# 1-Controller.net
KiCad netlist of a schematic drawn in Altium Designer
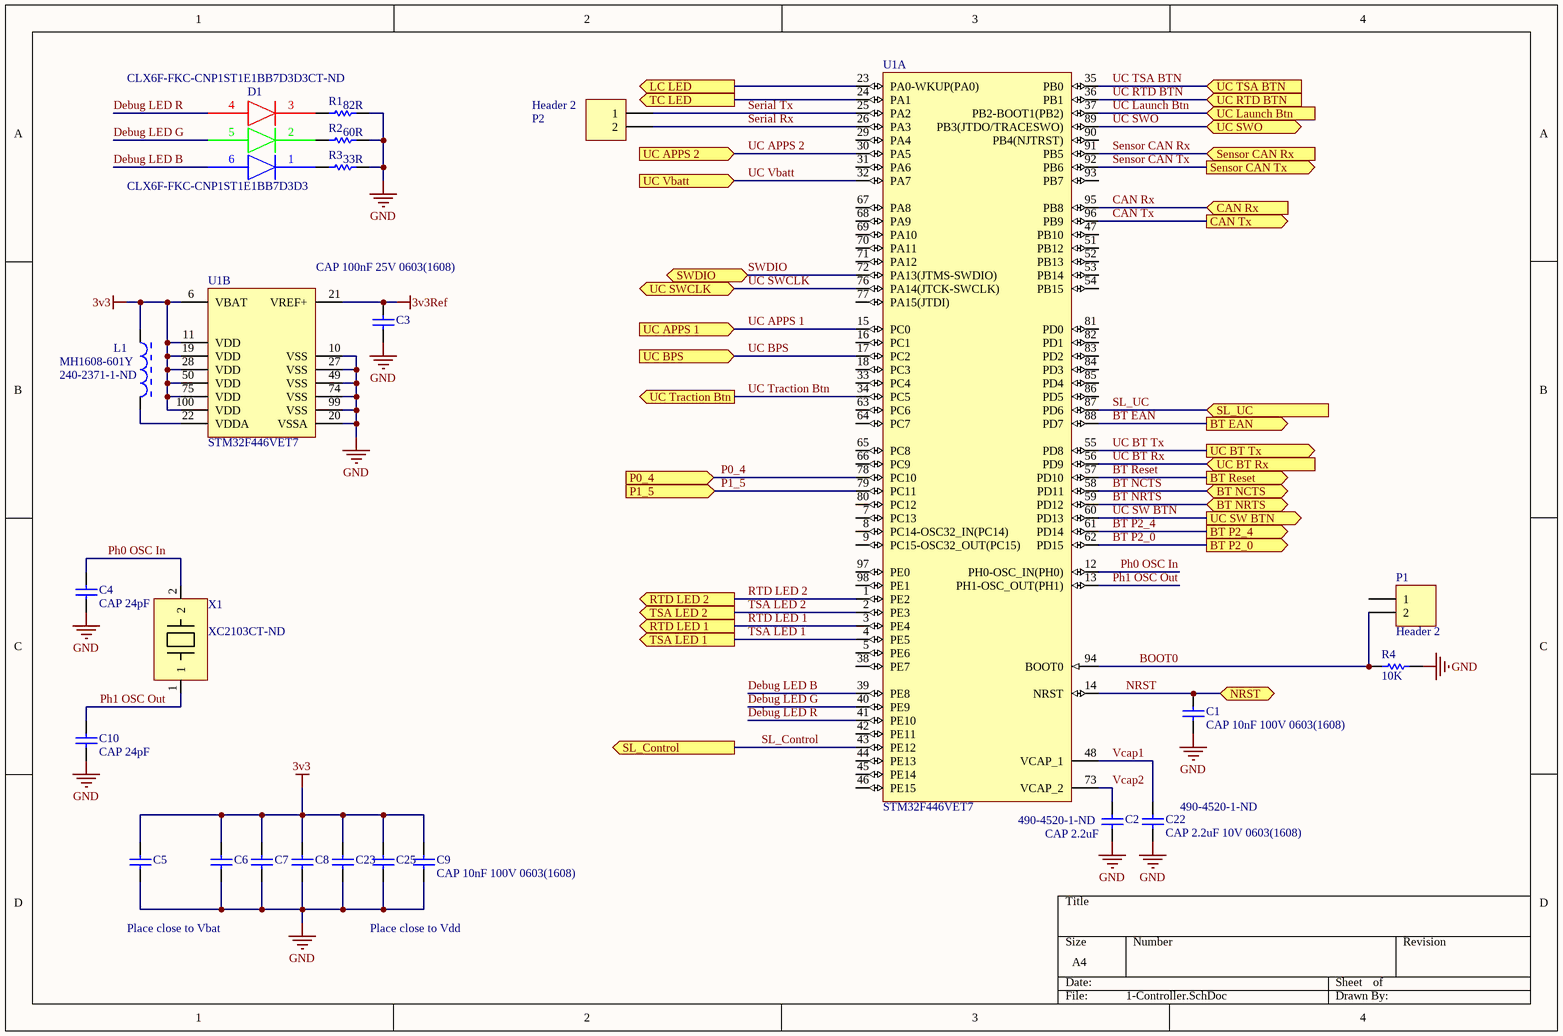
[diagram p0: 1-Controller.SchDoc]

(export (version "E")
  (design (tool "Eeschema 10.0.6"))
  (components
    (comp (ref "C1")
      (value "CAP 10nF 100V 0603(1608)")
      (footprint "CAPC0603(1608)100_M")
      (description "CAP 10nF 100V ±20% 0603 (1608 Metric) Thickness 1mm SMD")
      (fields (field (name "TOLERANCE") "Â±20%"))
      (libsource (lib "Altium Content Vault") (part "CAP"))
    )
    (comp (ref "C2")
      (value "CAP 2.2uF")
      (footprint "CAPC0603(1608)55_N")
      (description "CAP 2.2uF 10V ±10% 0603 (1608 Metric) Thickness 0.55mm SMD")
      (fields (field (name "TOLERANCE") "Â±10%") (field (name "SUPPLIER PART NUMBER 1") "490-4520-1-ND"))
      (libsource (lib "Altium Content Vault") (part "CAP"))
    )
    (comp (ref "C3")
      (value "CAP 100nF 25V 0603(1608)")
      (footprint "CAPC0603(1608)100_N")
      (description "CAP 100nF 25V ±20% 0603 (1608 Metric) Thickness 1mm SMD")
      (fields (field (name "TOLERANCE") "Â±20%"))
      (libsource (lib "Altium Content Vault") (part "CAP"))
    )
    (comp (ref "C4")
      (value "CAP 24pF")
      (footprint "CAPC0603(1608)100_N")
      (description "CAP 24pF 16V ±2% 0603 (1608 Metric) Thickness 1mm SMD")
      (fields (field (name "TOLERANCE") "Â±2%"))
      (libsource (lib "Altium Content Vault") (part "CAP"))
    )
    (comp (ref "C5")
      (value "CAP 10nF 100V 0603(1608)")
      (footprint "CAPC0603(1608)100_M")
      (description "CAP 10nF 100V ±20% 0603 (1608 Metric) Thickness 1mm SMD")
      (fields (field (name "TOLERANCE") "Â±20%"))
      (libsource (lib "Altium Content Vault") (part "CAP"))
    )
    (comp (ref "C6")
      (value "CAP 10nF 100V 0603(1608)")
      (footprint "CAPC0603(1608)100_M")
      (description "CAP 10nF 100V ±20% 0603 (1608 Metric) Thickness 1mm SMD")
      (fields (field (name "TOLERANCE") "Â±20%"))
      (libsource (lib "Altium Content Vault") (part "CAP"))
    )
    (comp (ref "C7")
      (value "CAP 10nF 100V 0603(1608)")
      (footprint "CAPC0603(1608)100_M")
      (description "CAP 10nF 100V ±20% 0603 (1608 Metric) Thickness 1mm SMD")
      (fields (field (name "TOLERANCE") "Â±20%"))
      (libsource (lib "Altium Content Vault") (part "CAP"))
    )
    (comp (ref "C8")
      (value "CAP 10nF 100V 0603(1608)")
      (footprint "CAPC0603(1608)100_M")
      (description "CAP 10nF 100V ±20% 0603 (1608 Metric) Thickness 1mm SMD")
      (fields (field (name "TOLERANCE") "Â±20%"))
      (libsource (lib "Altium Content Vault") (part "CAP"))
    )
    (comp (ref "C9")
      (value "CAP 10nF 100V 0603(1608)")
      (footprint "CAPC0603(1608)100_M")
      (description "CAP 10nF 100V ±20% 0603 (1608 Metric) Thickness 1mm SMD")
      (fields (field (name "TOLERANCE") "Â±20%"))
      (libsource (lib "Altium Content Vault") (part "CAP"))
    )
    (comp (ref "C10")
      (value "CAP 24pF")
      (footprint "CAPC0603(1608)100_N")
      (description "CAP 24pF 16V ±2% 0603 (1608 Metric) Thickness 1mm SMD")
      (fields (field (name "TOLERANCE") "Â±2%"))
      (libsource (lib "Altium Content Vault") (part "CAP"))
    )
    (comp (ref "C22")
      (value "CAP 2.2uF 10V 0603(1608)")
      (footprint "CAPC0603(1608)55_N")
      (description "CAP 2.2uF 10V ±10% 0603 (1608 Metric) Thickness 0.55mm SMD")
      (fields (field (name "TOLERANCE") "Â±10%") (field (name "SUPPLIER PART NUMBER 1") "490-4520-1-ND"))
      (libsource (lib "Altium Content Vault") (part "CAP"))
    )
    (comp (ref "C23")
      (value "CAP 10nF 100V 0603(1608)")
      (footprint "CAPC0603(1608)100_M")
      (description "CAP 10nF 100V ±20% 0603 (1608 Metric) Thickness 1mm SMD")
      (fields (field (name "TOLERANCE") "Â±20%"))
      (libsource (lib "Altium Content Vault") (part "CAP"))
    )
    (comp (ref "C25")
      (value "CAP 10nF 100V 0603(1608)")
      (footprint "CAPC0603(1608)100_M")
      (description "CAP 10nF 100V ±20% 0603 (1608 Metric) Thickness 1mm SMD")
      (fields (field (name "TOLERANCE") "Â±20%"))
      (libsource (lib "Altium Content Vault") (part "CAP"))
    )
    (comp (ref "D1")
      (value "CLX6F-FKC-CNP1ST1E1BB7D3D3")
      (footprint "CLX6C-FKB")
      (fields (field (name "SUPPLIER PART NUMBER 1") "CLX6F-FKC-CNP1ST1E1BB7D3D3CT-ND"))
      (libsource (lib "VCB_2019") (part "LED - CLX6F-FKC-CNP1ST1E1BB7D3D3"))
    )
    (comp (ref "L1")
      (value "MH1608-601Y")
      (footprint "BOUR-MH1608_V")
      (description "Chip Bead, 600 Ohm, 1 A, -55 to 125 degC, 2-Pin SMD (0603), RoHS, Tape and Reel")
      (fields (field (name "MANUFACTURER") "Bourns") (field (name "SUPPLIER PART NUMBER 1") "240-2371-1-ND"))
      (libsource (lib "Altium Content Vault") (part "IND-FB-2"))
    )
    (comp (ref "P1")
      (value "Header 2")
      (footprint "HDR1X2")
      (description "Header, 2-Pin")
      (fields (field (name "PUBLISHER") "Altium Limited"))
      (libsource (lib "Miscellaneous Connectors") (part "Header 2"))
    )
    (comp (ref "P2")
      (value "Header 2")
      (footprint "HDR1X2")
      (description "Header, 2-Pin")
      (fields (field (name "PUBLISHER") "Altium Limited"))
      (libsource (lib "") (part "Header 2_1"))
    )
    (comp (ref "R1")
      (value "82R")
      (footprint "RESC0603(1608)_N")
      (description "82R 0.1W 5% 0603 (1608 Metric)  SMD")
      (fields (field (name "TOLERANCE") "5 %") (field (name "POWER") "0.1 W"))
      (libsource (lib "Altium Content Vault") (part "RES"))
    )
    (comp (ref "R2")
      (value "60R")
      (footprint "RESC0603(1608)_N")
      (description "60R4 0.1W 1% 0603 (1608 Metric)  SMD")
      (fields (field (name "TOLERANCE") "1 %") (field (name "POWER") "0.1 W"))
      (libsource (lib "Altium Content Vault") (part "RES"))
    )
    (comp (ref "R3")
      (value "33R")
      (footprint "RESC0603(1608)_N")
      (description "33R 0.1W 5% 0603 (1608 Metric)  SMD")
      (fields (field (name "TOLERANCE") "5 %") (field (name "POWER") "0.1 W"))
      (libsource (lib "Altium Content Vault") (part "RES"))
    )
    (comp (ref "R4")
      (value "10K")
      (footprint "RESC0603(1608)_N")
      (description "10K 0.1W 5% 0603 (1608 Metric)  SMD")
      (fields (field (name "TOLERANCE") "5 %") (field (name "POWER") "0.1 W"))
      (libsource (lib "Altium Content Vault") (part "RES"))
    )
    (comp (ref "U1")
      (value "STM32F446VET7")
      (footprint "STM-LQFP100_L")
      (libsource (lib "Altium Content Vault") (part "MC-ARM-STM32F446-LQFP100"))
    )
    (comp (ref "X1")
      (value "7A-8.000MAAJ-T")
      (footprint "2-SMD, No Lead")
      (fields
        (field (name "MANUFACTURER") "TXC CORPORATION")
        (field (name "SUPPLIER PART NUMBER 1") "XC2103CT-ND")
      )
      (libsource (lib "VCU Library") (part "8MHz crystal, 7A-8.000MAAJ-T"))
    )
  )
  (nets
    (net (code "1") (name "/BOOT0") (class "Default")
      (node (ref "P1") (pin "2") (pinfunction "2_2") (pintype "passive"))
      (node (ref "R4") (pin "1") (pinfunction "1_1") (pintype "passive"))
      (node (ref "U1") (pin "94") (pinfunction "BOOT0_94") (pintype "input"))
    )
    (net (code "2") (name "/BT EAN") (class "Default")
      (node (ref "U1") (pin "88") (pinfunction "PD7_88") (pintype "bidirectional"))
    )
    (net (code "3") (name "/BT NCTS") (class "Default")
      (node (ref "U1") (pin "58") (pinfunction "PD11_58") (pintype "bidirectional"))
    )
    (net (code "4") (name "/BT NRTS") (class "Default")
      (node (ref "U1") (pin "59") (pinfunction "PD12_59") (pintype "bidirectional"))
    )
    (net (code "5") (name "/BT P2_0") (class "Default")
      (node (ref "U1") (pin "62") (pinfunction "PD15_62") (pintype "bidirectional"))
    )
    (net (code "6") (name "/BT P2_4") (class "Default")
      (node (ref "U1") (pin "61") (pinfunction "PD14_61") (pintype "bidirectional"))
    )
    (net (code "7") (name "/BT Reset") (class "Default")
      (node (ref "U1") (pin "57") (pinfunction "PD10_57") (pintype "bidirectional"))
    )
    (net (code "8") (name "/CAN Rx") (class "Default")
      (node (ref "U1") (pin "95") (pinfunction "PB8_95") (pintype "bidirectional"))
    )
    (net (code "9") (name "/CAN Tx") (class "Default")
      (node (ref "U1") (pin "96") (pinfunction "PB9_96") (pintype "bidirectional"))
    )
    (net (code "10") (name "/Debug LED B") (class "Default")
      (node (ref "D1") (pin "6") (pinfunction "B_6") (pintype "passive"))
      (node (ref "U1") (pin "39") (pinfunction "PE8_39") (pintype "bidirectional"))
    )
    (net (code "11") (name "/Debug LED G") (class "Default")
      (node (ref "D1") (pin "5") (pinfunction "G_5") (pintype "passive"))
      (node (ref "U1") (pin "40") (pinfunction "PE9_40") (pintype "bidirectional"))
    )
    (net (code "12") (name "/Debug LED R") (class "Default")
      (node (ref "D1") (pin "4") (pinfunction "R_4") (pintype "passive"))
      (node (ref "U1") (pin "41") (pinfunction "PE10_41") (pintype "bidirectional"))
    )
    (net (code "13") (name "/LC LED") (class "Default")
      (node (ref "U1") (pin "23") (pinfunction "PA0-WKUP(PA0)_23") (pintype "bidirectional"))
    )
    (net (code "14") (name "/NRST") (class "Default")
      (node (ref "C1") (pin "2") (pinfunction "2_2") (pintype "passive"))
      (node (ref "U1") (pin "14") (pinfunction "NRST_14") (pintype "bidirectional"))
    )
    (net (code "15") (name "/P0_4") (class "Default")
      (node (ref "U1") (pin "78") (pinfunction "PC10_78") (pintype "bidirectional"))
    )
    (net (code "16") (name "/P1_5") (class "Default")
      (node (ref "U1") (pin "79") (pinfunction "PC11_79") (pintype "bidirectional"))
    )
    (net (code "17") (name "/Ph0 OSC In") (class "Default")
      (node (ref "C4") (pin "2") (pinfunction "2_2") (pintype "passive"))
      (node (ref "U1") (pin "12") (pinfunction "PH0-OSC_IN(PH0)_12") (pintype "bidirectional"))
      (node (ref "X1") (pin "2") (pinfunction "2_2") (pintype "passive"))
    )
    (net (code "18") (name "/Ph1 OSC Out") (class "Default")
      (node (ref "C10") (pin "2") (pinfunction "2_2") (pintype "passive"))
      (node (ref "U1") (pin "13") (pinfunction "PH1-OSC_OUT(PH1)_13") (pintype "bidirectional"))
      (node (ref "X1") (pin "1") (pinfunction "1_1") (pintype "passive"))
    )
    (net (code "19") (name "/RTD LED 1") (class "Default")
      (node (ref "U1") (pin "3") (pinfunction "PE4_3") (pintype "bidirectional"))
    )
    (net (code "20") (name "/RTD LED 2") (class "Default")
      (node (ref "U1") (pin "1") (pinfunction "PE2_1") (pintype "bidirectional"))
    )
    (net (code "21") (name "/SL_Control") (class "Default")
      (node (ref "U1") (pin "43") (pinfunction "PE12_43") (pintype "bidirectional"))
    )
    (net (code "22") (name "/SL_UC") (class "Default")
      (node (ref "U1") (pin "87") (pinfunction "PD6_87") (pintype "bidirectional"))
    )
    (net (code "23") (name "/SWDIO") (class "Default")
      (node (ref "U1") (pin "72") (pinfunction "PA13(JTMS-SWDIO)_72") (pintype "bidirectional"))
    )
    (net (code "24") (name "/Sensor CAN Rx") (class "Default")
      (node (ref "U1") (pin "91") (pinfunction "PB5_91") (pintype "bidirectional"))
    )
    (net (code "25") (name "/Sensor CAN Tx") (class "Default")
      (node (ref "U1") (pin "92") (pinfunction "PB6_92") (pintype "bidirectional"))
    )
    (net (code "26") (name "/Serial Rx") (class "Default")
      (node (ref "P2") (pin "2") (pinfunction "2_2") (pintype "passive"))
      (node (ref "U1") (pin "26") (pinfunction "PA3_26") (pintype "bidirectional"))
    )
    (net (code "27") (name "/Serial Tx") (class "Default")
      (node (ref "P2") (pin "1") (pinfunction "1_1") (pintype "passive"))
      (node (ref "U1") (pin "25") (pinfunction "PA2_25") (pintype "bidirectional"))
    )
    (net (code "28") (name "/TC LED") (class "Default")
      (node (ref "U1") (pin "24") (pinfunction "PA1_24") (pintype "bidirectional"))
    )
    (net (code "29") (name "/TSA LED 1") (class "Default")
      (node (ref "U1") (pin "4") (pinfunction "PE5_4") (pintype "bidirectional"))
    )
    (net (code "30") (name "/TSA LED 2") (class "Default")
      (node (ref "U1") (pin "2") (pinfunction "PE3_2") (pintype "bidirectional"))
    )
    (net (code "31") (name "/UC APPS 1") (class "Default")
      (node (ref "U1") (pin "15") (pinfunction "PC0_15") (pintype "bidirectional"))
    )
    (net (code "32") (name "/UC APPS 2") (class "Default")
      (node (ref "U1") (pin "30") (pinfunction "PA5_30") (pintype "bidirectional"))
    )
    (net (code "33") (name "/UC BPS") (class "Default")
      (node (ref "U1") (pin "17") (pinfunction "PC2_17") (pintype "bidirectional"))
    )
    (net (code "34") (name "/UC BT Rx") (class "Default")
      (node (ref "U1") (pin "56") (pinfunction "PD9_56") (pintype "bidirectional"))
    )
    (net (code "35") (name "/UC BT Tx") (class "Default")
      (node (ref "U1") (pin "55") (pinfunction "PD8_55") (pintype "bidirectional"))
    )
    (net (code "36") (name "/UC Launch Btn") (class "Default")
      (node (ref "U1") (pin "37") (pinfunction "PB2-BOOT1(PB2)_37") (pintype "bidirectional"))
    )
    (net (code "37") (name "/UC RTD BTN") (class "Default")
      (node (ref "U1") (pin "36") (pinfunction "PB1_36") (pintype "bidirectional"))
    )
    (net (code "38") (name "/UC SW BTN") (class "Default")
      (node (ref "U1") (pin "60") (pinfunction "PD13_60") (pintype "bidirectional"))
    )
    (net (code "39") (name "/UC SWCLK") (class "Default")
      (node (ref "U1") (pin "76") (pinfunction "PA14(JTCK-SWCLK)_76") (pintype "bidirectional"))
    )
    (net (code "40") (name "/UC SWO") (class "Default")
      (node (ref "U1") (pin "89") (pinfunction "PB3(JTDO/TRACESWO)_89") (pintype "bidirectional"))
    )
    (net (code "41") (name "/UC TSA BTN") (class "Default")
      (node (ref "U1") (pin "35") (pinfunction "PB0_35") (pintype "bidirectional"))
    )
    (net (code "42") (name "/UC Traction Btn") (class "Default")
      (node (ref "U1") (pin "34") (pinfunction "PC5_34") (pintype "bidirectional"))
    )
    (net (code "43") (name "/UC Vbatt") (class "Default")
      (node (ref "U1") (pin "32") (pinfunction "PA7_32") (pintype "bidirectional"))
    )
    (net (code "44") (name "/Vcap1") (class "Default")
      (node (ref "C22") (pin "2") (pinfunction "2_2") (pintype "passive"))
      (node (ref "U1") (pin "48") (pinfunction "VCAP_1_48") (pintype "passive"))
    )
    (net (code "45") (name "/Vcap2") (class "Default")
      (node (ref "C2") (pin "2") (pinfunction "2_2") (pintype "passive"))
      (node (ref "U1") (pin "73") (pinfunction "VCAP_2_73") (pintype "passive"))
    )
    (net (code "46") (name "3v3") (class "Default")
      (node (ref "C23") (pin "2") (pinfunction "2_2") (pintype "passive"))
      (node (ref "C25") (pin "2") (pinfunction "2_2") (pintype "passive"))
      (node (ref "C5") (pin "2") (pinfunction "2_2") (pintype "passive"))
      (node (ref "C6") (pin "2") (pinfunction "2_2") (pintype "passive"))
      (node (ref "C7") (pin "2") (pinfunction "2_2") (pintype "passive"))
      (node (ref "C8") (pin "2") (pinfunction "2_2") (pintype "passive"))
      (node (ref "C9") (pin "2") (pinfunction "2_2") (pintype "passive"))
      (node (ref "L1") (pin "1") (pinfunction "1_1") (pintype "passive"))
      (node (ref "U1") (pin "100") (pinfunction "VDD_100") (pintype "power_in"))
      (node (ref "U1") (pin "11") (pinfunction "VDD_11") (pintype "power_in"))
      (node (ref "U1") (pin "19") (pinfunction "VDD_19") (pintype "power_in"))
      (node (ref "U1") (pin "28") (pinfunction "VDD_28") (pintype "power_in"))
      (node (ref "U1") (pin "50") (pinfunction "VDD_50") (pintype "power_in"))
      (node (ref "U1") (pin "6") (pinfunction "VBAT_6") (pintype "power_in"))
      (node (ref "U1") (pin "75") (pinfunction "VDD_75") (pintype "power_in"))
    )
    (net (code "47") (name "3v3Ref") (class "Default")
      (node (ref "C3") (pin "2") (pinfunction "2_2") (pintype "passive"))
      (node (ref "U1") (pin "21") (pinfunction "VREF+_21") (pintype "power_in"))
    )
    (net (code "48") (name "GND") (class "Default")
      (node (ref "C1") (pin "1") (pinfunction "1_1") (pintype "passive"))
      (node (ref "C10") (pin "1") (pinfunction "1_1") (pintype "passive"))
      (node (ref "C2") (pin "1") (pinfunction "1_1") (pintype "passive"))
      (node (ref "C22") (pin "1") (pinfunction "1_1") (pintype "passive"))
      (node (ref "C23") (pin "1") (pinfunction "1_1") (pintype "passive"))
      (node (ref "C25") (pin "1") (pinfunction "1_1") (pintype "passive"))
      (node (ref "C3") (pin "1") (pinfunction "1_1") (pintype "passive"))
      (node (ref "C4") (pin "1") (pinfunction "1_1") (pintype "passive"))
      (node (ref "C5") (pin "1") (pinfunction "1_1") (pintype "passive"))
      (node (ref "C6") (pin "1") (pinfunction "1_1") (pintype "passive"))
      (node (ref "C7") (pin "1") (pinfunction "1_1") (pintype "passive"))
      (node (ref "C8") (pin "1") (pinfunction "1_1") (pintype "passive"))
      (node (ref "C9") (pin "1") (pinfunction "1_1") (pintype "passive"))
      (node (ref "R1") (pin "2") (pinfunction "2_2") (pintype "passive"))
      (node (ref "R2") (pin "2") (pinfunction "2_2") (pintype "passive"))
      (node (ref "R3") (pin "2") (pinfunction "2_2") (pintype "passive"))
      (node (ref "R4") (pin "2") (pinfunction "2_2") (pintype "passive"))
      (node (ref "U1") (pin "10") (pinfunction "VSS_10") (pintype "power_in"))
      (node (ref "U1") (pin "20") (pinfunction "VSSA_20") (pintype "power_in"))
      (node (ref "U1") (pin "27") (pinfunction "VSS_27") (pintype "power_in"))
      (node (ref "U1") (pin "49") (pinfunction "VSS_49") (pintype "power_in"))
      (node (ref "U1") (pin "74") (pinfunction "VSS_74") (pintype "power_in"))
      (node (ref "U1") (pin "99") (pinfunction "VSS_99") (pintype "power_in"))
    )
    (net (code "49") (name "Net-(D1-B-Pad1)") (class "Default")
      (node (ref "D1") (pin "1") (pinfunction "B_1") (pintype "passive"))
      (node (ref "R3") (pin "1") (pinfunction "1_1") (pintype "passive"))
    )
    (net (code "50") (name "Net-(D1-G-Pad2)") (class "Default")
      (node (ref "D1") (pin "2") (pinfunction "G_2") (pintype "passive"))
      (node (ref "R2") (pin "1") (pinfunction "1_1") (pintype "passive"))
    )
    (net (code "51") (name "Net-(D1-R-Pad3)") (class "Default")
      (node (ref "D1") (pin "3") (pinfunction "R_3") (pintype "passive"))
      (node (ref "R1") (pin "1") (pinfunction "1_1") (pintype "passive"))
    )
    (net (code "52") (name "Net-(U1B-VDDA)") (class "Default")
      (node (ref "L1") (pin "2") (pinfunction "2_2") (pintype "passive"))
      (node (ref "U1") (pin "22") (pinfunction "VDDA_22") (pintype "power_in"))
    )
    (net (code "53") (name "unconnected-(P1-Pad1)") (class "Default")
      (node (ref "P1") (pin "1") (pinfunction "1_1") (pintype "passive"))
    )
    (net (code "54") (name "unconnected-(U1A-PA4-Pad29)") (class "Default")
      (node (ref "U1") (pin "29") (pinfunction "PA4_29") (pintype "bidirectional"))
    )
    (net (code "55") (name "unconnected-(U1A-PA6-Pad31)") (class "Default")
      (node (ref "U1") (pin "31") (pinfunction "PA6_31") (pintype "bidirectional"))
    )
    (net (code "56") (name "unconnected-(U1A-PA8-Pad67)") (class "Default")
      (node (ref "U1") (pin "67") (pinfunction "PA8_67") (pintype "bidirectional"))
    )
    (net (code "57") (name "unconnected-(U1A-PA9-Pad68)") (class "Default")
      (node (ref "U1") (pin "68") (pinfunction "PA9_68") (pintype "bidirectional"))
    )
    (net (code "58") (name "unconnected-(U1A-PA10-Pad69)") (class "Default")
      (node (ref "U1") (pin "69") (pinfunction "PA10_69") (pintype "bidirectional"))
    )
    (net (code "59") (name "unconnected-(U1A-PA11-Pad70)") (class "Default")
      (node (ref "U1") (pin "70") (pinfunction "PA11_70") (pintype "bidirectional"))
    )
    (net (code "60") (name "unconnected-(U1A-PA12-Pad71)") (class "Default")
      (node (ref "U1") (pin "71") (pinfunction "PA12_71") (pintype "bidirectional"))
    )
    (net (code "61") (name "unconnected-(U1A-PA15(JTDI)-Pad77)") (class "Default")
      (node (ref "U1") (pin "77") (pinfunction "PA15(JTDI)_77") (pintype "bidirectional"))
    )
    (net (code "62") (name "unconnected-(U1A-PB4(NJTRST)-Pad90)") (class "Default")
      (node (ref "U1") (pin "90") (pinfunction "PB4(NJTRST)_90") (pintype "bidirectional"))
    )
    (net (code "63") (name "unconnected-(U1A-PB7-Pad93)") (class "Default")
      (node (ref "U1") (pin "93") (pinfunction "PB7_93") (pintype "bidirectional"))
    )
    (net (code "64") (name "unconnected-(U1A-PB10-Pad47)") (class "Default")
      (node (ref "U1") (pin "47") (pinfunction "PB10_47") (pintype "bidirectional"))
    )
    (net (code "65") (name "unconnected-(U1A-PB12-Pad51)") (class "Default")
      (node (ref "U1") (pin "51") (pinfunction "PB12_51") (pintype "bidirectional"))
    )
    (net (code "66") (name "unconnected-(U1A-PB13-Pad52)") (class "Default")
      (node (ref "U1") (pin "52") (pinfunction "PB13_52") (pintype "bidirectional"))
    )
    (net (code "67") (name "unconnected-(U1A-PB14-Pad53)") (class "Default")
      (node (ref "U1") (pin "53") (pinfunction "PB14_53") (pintype "bidirectional"))
    )
    (net (code "68") (name "unconnected-(U1A-PB15-Pad54)") (class "Default")
      (node (ref "U1") (pin "54") (pinfunction "PB15_54") (pintype "bidirectional"))
    )
    (net (code "69") (name "unconnected-(U1A-PC1-Pad16)") (class "Default")
      (node (ref "U1") (pin "16") (pinfunction "PC1_16") (pintype "bidirectional"))
    )
    (net (code "70") (name "unconnected-(U1A-PC3-Pad18)") (class "Default")
      (node (ref "U1") (pin "18") (pinfunction "PC3_18") (pintype "bidirectional"))
    )
    (net (code "71") (name "unconnected-(U1A-PC4-Pad33)") (class "Default")
      (node (ref "U1") (pin "33") (pinfunction "PC4_33") (pintype "bidirectional"))
    )
    (net (code "72") (name "unconnected-(U1A-PC6-Pad63)") (class "Default")
      (node (ref "U1") (pin "63") (pinfunction "PC6_63") (pintype "bidirectional"))
    )
    (net (code "73") (name "unconnected-(U1A-PC7-Pad64)") (class "Default")
      (node (ref "U1") (pin "64") (pinfunction "PC7_64") (pintype "bidirectional"))
    )
    (net (code "74") (name "unconnected-(U1A-PC8-Pad65)") (class "Default")
      (node (ref "U1") (pin "65") (pinfunction "PC8_65") (pintype "bidirectional"))
    )
    (net (code "75") (name "unconnected-(U1A-PC9-Pad66)") (class "Default")
      (node (ref "U1") (pin "66") (pinfunction "PC9_66") (pintype "bidirectional"))
    )
    (net (code "76") (name "unconnected-(U1A-PC12-Pad80)") (class "Default")
      (node (ref "U1") (pin "80") (pinfunction "PC12_80") (pintype "bidirectional"))
    )
    (net (code "77") (name "unconnected-(U1A-PC13-Pad7)") (class "Default")
      (node (ref "U1") (pin "7") (pinfunction "PC13_7") (pintype "bidirectional"))
    )
    (net (code "78") (name "unconnected-(U1A-PC14-OSC32_IN(PC14)-Pad8)") (class "Default")
      (node (ref "U1") (pin "8") (pinfunction "PC14-OSC32_IN(PC14)_8") (pintype "bidirectional"))
    )
    (net (code "79") (name "unconnected-(U1A-PC15-OSC32_OUT(PC15)-Pad9)") (class "Default")
      (node (ref "U1") (pin "9") (pinfunction "PC15-OSC32_OUT(PC15)_9") (pintype "bidirectional"))
    )
    (net (code "80") (name "unconnected-(U1A-PD0-Pad81)") (class "Default")
      (node (ref "U1") (pin "81") (pinfunction "PD0_81") (pintype "bidirectional"))
    )
    (net (code "81") (name "unconnected-(U1A-PD1-Pad82)") (class "Default")
      (node (ref "U1") (pin "82") (pinfunction "PD1_82") (pintype "bidirectional"))
    )
    (net (code "82") (name "unconnected-(U1A-PD2-Pad83)") (class "Default")
      (node (ref "U1") (pin "83") (pinfunction "PD2_83") (pintype "bidirectional"))
    )
    (net (code "83") (name "unconnected-(U1A-PD3-Pad84)") (class "Default")
      (node (ref "U1") (pin "84") (pinfunction "PD3_84") (pintype "bidirectional"))
    )
    (net (code "84") (name "unconnected-(U1A-PD4-Pad85)") (class "Default")
      (node (ref "U1") (pin "85") (pinfunction "PD4_85") (pintype "bidirectional"))
    )
    (net (code "85") (name "unconnected-(U1A-PD5-Pad86)") (class "Default")
      (node (ref "U1") (pin "86") (pinfunction "PD5_86") (pintype "bidirectional"))
    )
    (net (code "86") (name "unconnected-(U1A-PE0-Pad97)") (class "Default")
      (node (ref "U1") (pin "97") (pinfunction "PE0_97") (pintype "bidirectional"))
    )
    (net (code "87") (name "unconnected-(U1A-PE1-Pad98)") (class "Default")
      (node (ref "U1") (pin "98") (pinfunction "PE1_98") (pintype "bidirectional"))
    )
    (net (code "88") (name "unconnected-(U1A-PE6-Pad5)") (class "Default")
      (node (ref "U1") (pin "5") (pinfunction "PE6_5") (pintype "bidirectional"))
    )
    (net (code "89") (name "unconnected-(U1A-PE7-Pad38)") (class "Default")
      (node (ref "U1") (pin "38") (pinfunction "PE7_38") (pintype "bidirectional"))
    )
    (net (code "90") (name "unconnected-(U1A-PE11-Pad42)") (class "Default")
      (node (ref "U1") (pin "42") (pinfunction "PE11_42") (pintype "bidirectional"))
    )
    (net (code "91") (name "unconnected-(U1A-PE13-Pad44)") (class "Default")
      (node (ref "U1") (pin "44") (pinfunction "PE13_44") (pintype "bidirectional"))
    )
    (net (code "92") (name "unconnected-(U1A-PE14-Pad45)") (class "Default")
      (node (ref "U1") (pin "45") (pinfunction "PE14_45") (pintype "bidirectional"))
    )
    (net (code "93") (name "unconnected-(U1A-PE15-Pad46)") (class "Default")
      (node (ref "U1") (pin "46") (pinfunction "PE15_46") (pintype "bidirectional"))
    )
  )
)
